# WaldoRevB.net
KiCad netlist of a schematic drawn in EAGLE
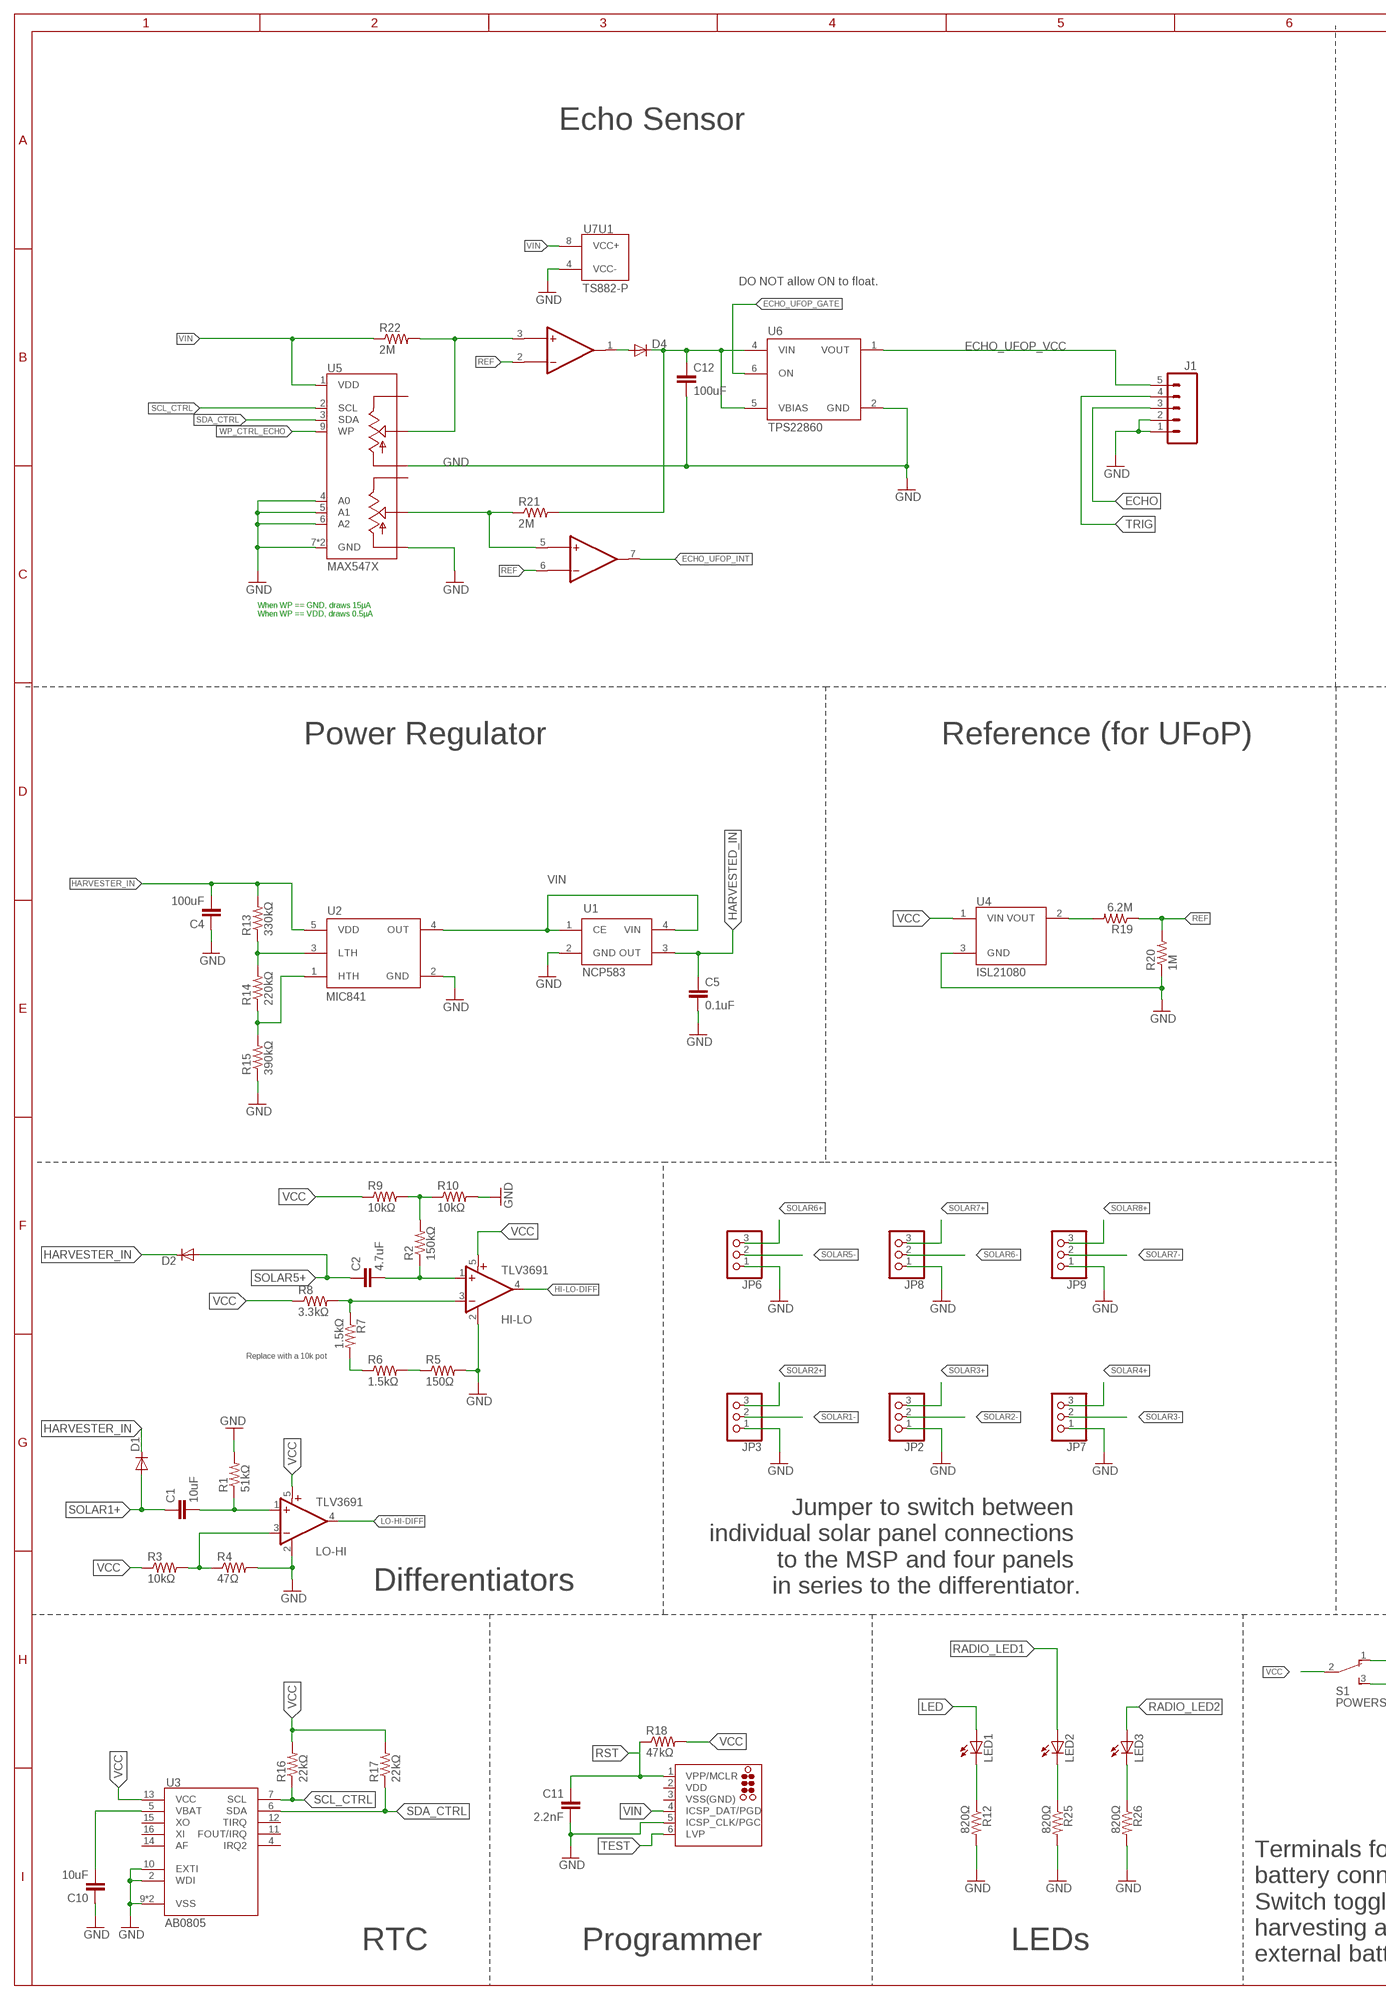
[diagram p0: schematic, sheet 1, part 1 of 2]
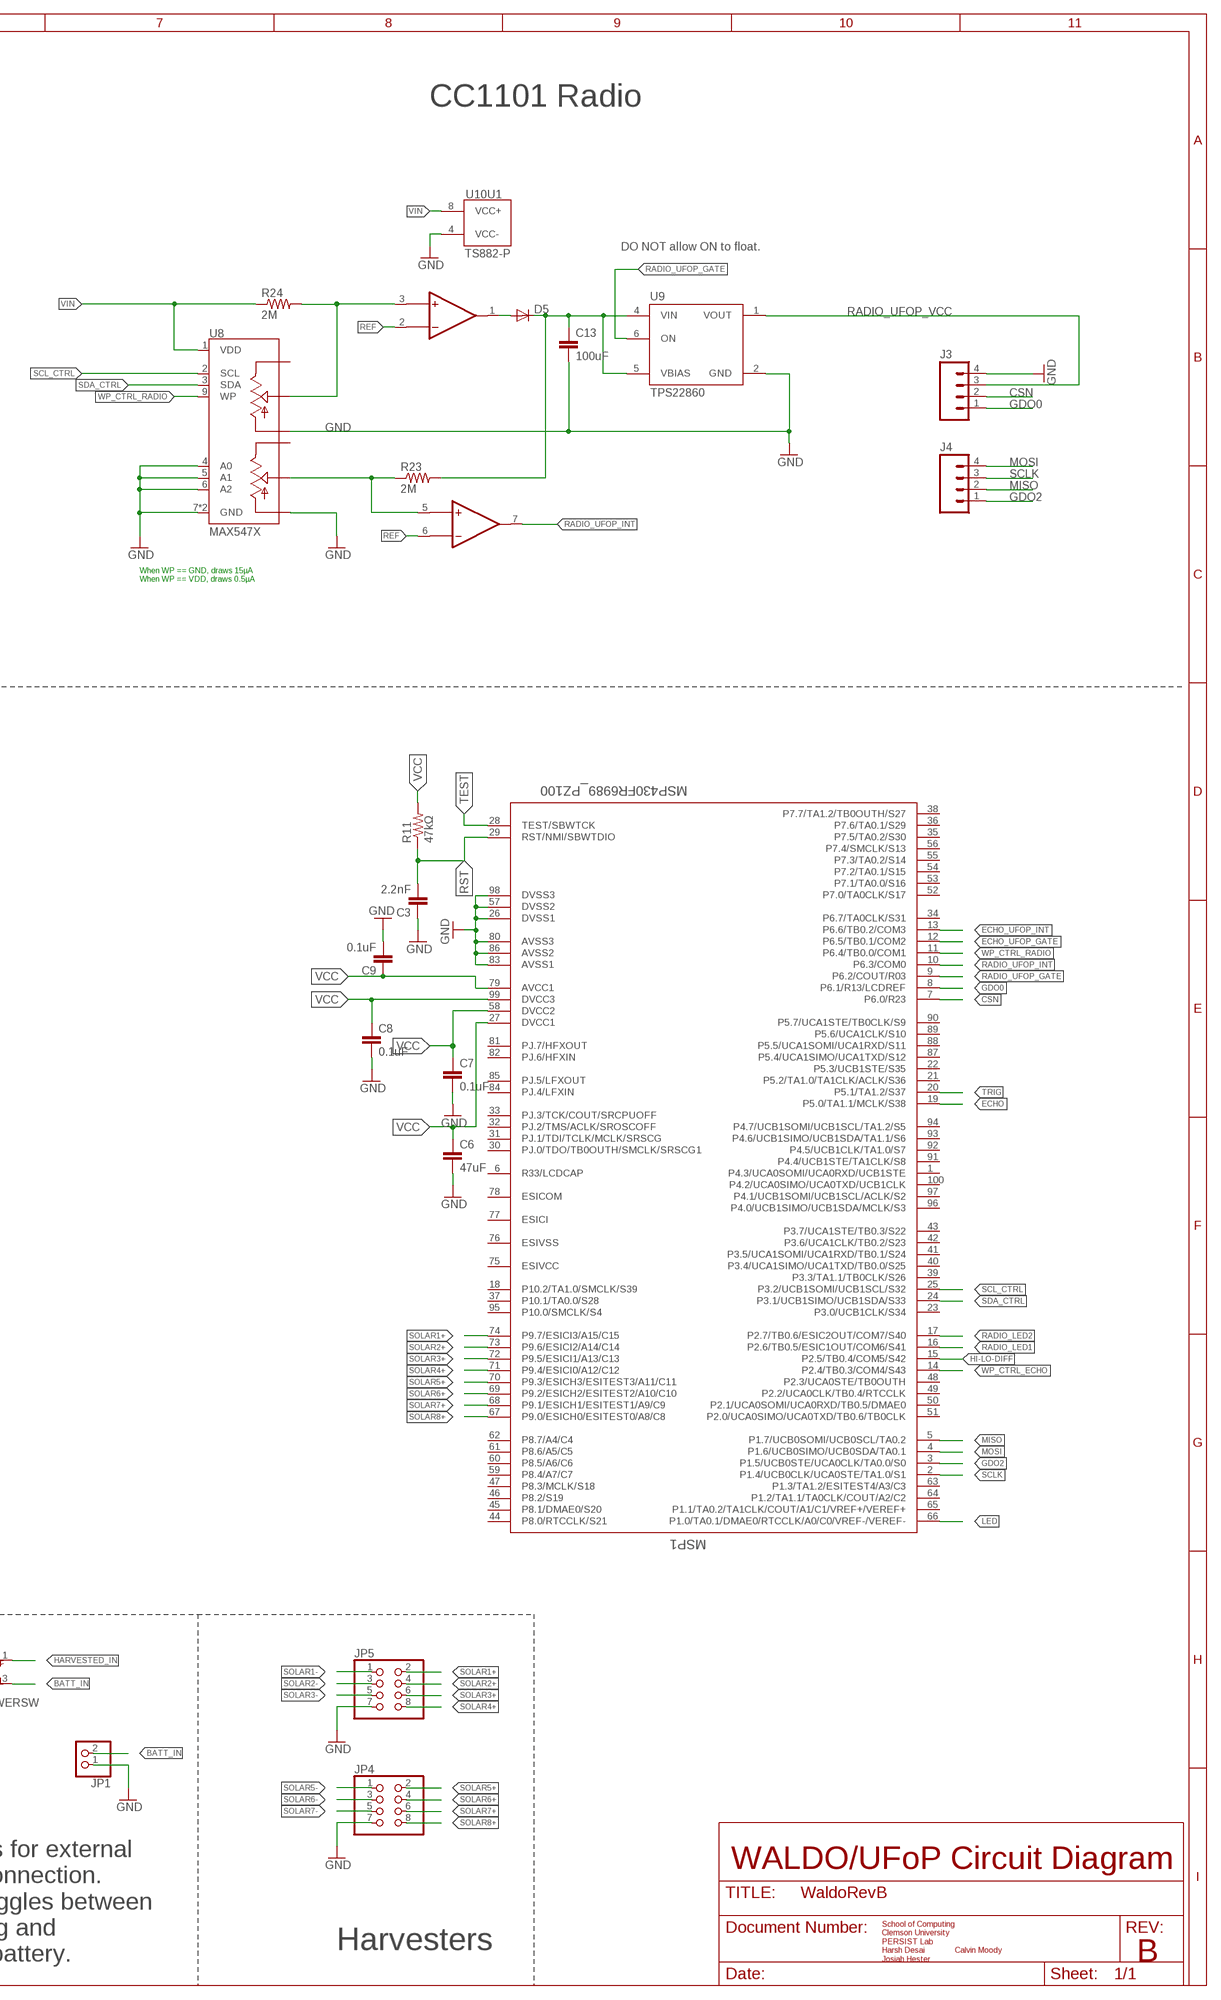
[diagram p1: schematic, sheet 1, part 2 of 2]

(export (version "E")
  (design (tool "Eeschema 10.0.6"))
  (components
    (comp (ref "C1")
      (value "10uF")
      (footprint "eagle-import:0805")
      (libsource (lib "eagle-import") (part "CAP0805"))
    )
    (comp (ref "C2")
      (value "4.7uF")
      (footprint "eagle-import:0805")
      (libsource (lib "eagle-import") (part "CAP0805"))
    )
    (comp (ref "C3")
      (value "2.2nF")
      (footprint "eagle-import:0805")
      (libsource (lib "eagle-import") (part "CAP0805"))
    )
    (comp (ref "C4")
      (value "100uF")
      (footprint "eagle-import:0805")
      (libsource (lib "eagle-import") (part "CAP0805"))
    )
    (comp (ref "C5")
      (value "0.1uF")
      (footprint "eagle-import:0805")
      (libsource (lib "eagle-import") (part "CAP0805"))
    )
    (comp (ref "C6")
      (value "47uF")
      (footprint "eagle-import:0805")
      (libsource (lib "eagle-import") (part "CAP0805"))
    )
    (comp (ref "C7")
      (value "0.1uF")
      (footprint "eagle-import:0805")
      (libsource (lib "eagle-import") (part "CAP0805"))
    )
    (comp (ref "C8")
      (value "0.1uF")
      (footprint "eagle-import:0805")
      (libsource (lib "eagle-import") (part "CAP0805"))
    )
    (comp (ref "C9")
      (value "0.1uF")
      (footprint "eagle-import:0805")
      (libsource (lib "eagle-import") (part "CAP0805"))
    )
    (comp (ref "C10")
      (value "10uF")
      (footprint "eagle-import:0805")
      (libsource (lib "eagle-import") (part "CAP0805"))
    )
    (comp (ref "C11")
      (value "2.2nF")
      (footprint "eagle-import:0805")
      (libsource (lib "eagle-import") (part "CAP0805"))
    )
    (comp (ref "C12")
      (value "100uF")
      (footprint "eagle-import:1210")
      (libsource (lib "eagle-import") (part "CAP1210"))
    )
    (comp (ref "C13")
      (value "100uF")
      (footprint "eagle-import:1210")
      (libsource (lib "eagle-import") (part "CAP1210"))
    )
    (comp (ref "D1")
      (value "DIODESOD523")
      (footprint "eagle-import:SOD523")
      (libsource (lib "eagle-import") (part "DIODESOD523"))
    )
    (comp (ref "D2")
      (value "DIODESOD523")
      (footprint "eagle-import:SOD523")
      (libsource (lib "eagle-import") (part "DIODESOD523"))
    )
    (comp (ref "D4")
      (value "DIODESOD")
      (footprint "eagle-import:SOD-323")
      (libsource (lib "eagle-import") (part "DIODESOD"))
    )
    (comp (ref "D5")
      (value "DIODESOD")
      (footprint "eagle-import:SOD-323")
      (libsource (lib "eagle-import") (part "DIODESOD"))
    )
    (comp (ref "HI-LO")
      (value "TLV3691")
      (footprint "eagle-import:SC70-5")
      (libsource (lib "eagle-import") (part "TLV3691"))
    )
    (comp (ref "J1")
      (value "M05PTH")
      (footprint "eagle-import:1X05")
      (libsource (lib "eagle-import") (part "M05PTH"))
    )
    (comp (ref "J2")
      (value "TC2030-MCP-NL")
      (footprint "eagle-import:TC2030-MCP-NL")
      (libsource (lib "eagle-import") (part "TC2030-MCP-NL"))
    )
    (comp (ref "J3")
      (value "M04PTH")
      (footprint "eagle-import:1X04")
      (libsource (lib "eagle-import") (part "M04PTH"))
    )
    (comp (ref "J4")
      (value "M04PTH")
      (footprint "eagle-import:1X04")
      (libsource (lib "eagle-import") (part "M04PTH"))
    )
    (comp (ref "JP1")
      (value "PINHD-1X2")
      (footprint "eagle-import:1X02")
      (libsource (lib "eagle-import") (part "PINHD-1X2"))
    )
    (comp (ref "JP2")
      (value "PINHD-1X3")
      (footprint "eagle-import:1X03")
      (libsource (lib "eagle-import") (part "PINHD-1X3"))
    )
    (comp (ref "JP3")
      (value "PINHD-1X3")
      (footprint "eagle-import:1X03")
      (libsource (lib "eagle-import") (part "PINHD-1X3"))
    )
    (comp (ref "JP4")
      (value "PINHD-2X4")
      (footprint "eagle-import:2X04")
      (libsource (lib "eagle-import") (part "PINHD-2X4"))
    )
    (comp (ref "JP5")
      (value "PINHD-2X4")
      (footprint "eagle-import:2X04")
      (libsource (lib "eagle-import") (part "PINHD-2X4"))
    )
    (comp (ref "JP6")
      (value "PINHD-1X3")
      (footprint "eagle-import:1X03")
      (libsource (lib "eagle-import") (part "PINHD-1X3"))
    )
    (comp (ref "JP7")
      (value "PINHD-1X3")
      (footprint "eagle-import:1X03")
      (libsource (lib "eagle-import") (part "PINHD-1X3"))
    )
    (comp (ref "JP8")
      (value "PINHD-1X3")
      (footprint "eagle-import:1X03")
      (libsource (lib "eagle-import") (part "PINHD-1X3"))
    )
    (comp (ref "JP9")
      (value "PINHD-1X3")
      (footprint "eagle-import:1X03")
      (libsource (lib "eagle-import") (part "PINHD-1X3"))
    )
    (comp (ref "LED1")
      (value "LEDCHIP-LED0805")
      (footprint "eagle-import:CHIP-LED0805")
      (libsource (lib "eagle-import") (part "LEDCHIP-LED0805"))
    )
    (comp (ref "LED2")
      (value "LEDCHIP-LED0805")
      (footprint "eagle-import:CHIP-LED0805")
      (libsource (lib "eagle-import") (part "LEDCHIP-LED0805"))
    )
    (comp (ref "LED3")
      (value "LEDCHIP-LED0805")
      (footprint "eagle-import:CHIP-LED0805")
      (libsource (lib "eagle-import") (part "LEDCHIP-LED0805"))
    )
    (comp (ref "LO-HI")
      (value "TLV3691")
      (footprint "eagle-import:SC70-5")
      (libsource (lib "eagle-import") (part "TLV3691"))
    )
    (comp (ref "MSP1")
      (value "MSP430FR6989_PZ100")
      (footprint "eagle-import:PZ100")
      (libsource (lib "eagle-import") (part "MSP430FR6989_PZ100"))
    )
    (comp (ref "R1")
      (value "51kΩ")
      (footprint "eagle-import:M0805")
      (libsource (lib "eagle-import") (part "R-US_M0805"))
    )
    (comp (ref "R2")
      (value "150kΩ")
      (footprint "eagle-import:M0805")
      (libsource (lib "eagle-import") (part "R-US_M0805"))
    )
    (comp (ref "R3")
      (value "10kΩ")
      (footprint "eagle-import:M0805")
      (libsource (lib "eagle-import") (part "R-US_M0805"))
    )
    (comp (ref "R4")
      (value "47Ω")
      (footprint "eagle-import:M0805")
      (libsource (lib "eagle-import") (part "R-US_M0805"))
    )
    (comp (ref "R5")
      (value "150Ω")
      (footprint "eagle-import:M0805")
      (libsource (lib "eagle-import") (part "R-US_M0805"))
    )
    (comp (ref "R6")
      (value "1.5kΩ")
      (footprint "eagle-import:M0805")
      (libsource (lib "eagle-import") (part "R-US_M0805"))
    )
    (comp (ref "R7")
      (value "1.5kΩ")
      (footprint "eagle-import:M0805")
      (libsource (lib "eagle-import") (part "R-US_M0805"))
    )
    (comp (ref "R8")
      (value "3.3kΩ")
      (footprint "eagle-import:M0805")
      (libsource (lib "eagle-import") (part "R-US_M0805"))
    )
    (comp (ref "R9")
      (value "10kΩ")
      (footprint "eagle-import:M0805")
      (libsource (lib "eagle-import") (part "R-US_M0805"))
    )
    (comp (ref "R10")
      (value "10kΩ")
      (footprint "eagle-import:M0805")
      (libsource (lib "eagle-import") (part "R-US_M0805"))
    )
    (comp (ref "R11")
      (value "47kΩ")
      (footprint "eagle-import:M0805")
      (libsource (lib "eagle-import") (part "R-US_M0805"))
    )
    (comp (ref "R12")
      (value "820Ω")
      (footprint "eagle-import:M0805")
      (libsource (lib "eagle-import") (part "R-US_M0805"))
    )
    (comp (ref "R13")
      (value "330kΩ")
      (footprint "eagle-import:M0805")
      (libsource (lib "eagle-import") (part "R-US_M0805"))
    )
    (comp (ref "R14")
      (value "220kΩ")
      (footprint "eagle-import:M0805")
      (libsource (lib "eagle-import") (part "R-US_M0805"))
    )
    (comp (ref "R15")
      (value "390kΩ")
      (footprint "eagle-import:M0805")
      (libsource (lib "eagle-import") (part "R-US_M0805"))
    )
    (comp (ref "R16")
      (value "22kΩ")
      (footprint "eagle-import:M0805")
      (libsource (lib "eagle-import") (part "R-US_M0805"))
    )
    (comp (ref "R17")
      (value "22kΩ")
      (footprint "eagle-import:M0805")
      (libsource (lib "eagle-import") (part "R-US_M0805"))
    )
    (comp (ref "R18")
      (value "47kΩ")
      (footprint "eagle-import:M0805")
      (libsource (lib "eagle-import") (part "R-US_M0805"))
    )
    (comp (ref "R19")
      (value "6.2M")
      (footprint "eagle-import:0603")
      (libsource (lib "eagle-import") (part "R-EU0603"))
    )
    (comp (ref "R20")
      (value "1M")
      (footprint "eagle-import:0603")
      (libsource (lib "eagle-import") (part "R-EU0603"))
    )
    (comp (ref "R21")
      (value "2M")
      (footprint "eagle-import:0603")
      (libsource (lib "eagle-import") (part "R-EU0603"))
    )
    (comp (ref "R22")
      (value "2M")
      (footprint "eagle-import:0603")
      (libsource (lib "eagle-import") (part "R-EU0603"))
    )
    (comp (ref "R23")
      (value "2M")
      (footprint "eagle-import:0603")
      (libsource (lib "eagle-import") (part "R-EU0603"))
    )
    (comp (ref "R24")
      (value "2M")
      (footprint "eagle-import:0603")
      (libsource (lib "eagle-import") (part "R-EU0603"))
    )
    (comp (ref "R25")
      (value "820Ω")
      (footprint "eagle-import:M0805")
      (libsource (lib "eagle-import") (part "R-US_M0805"))
    )
    (comp (ref "R26")
      (value "820Ω")
      (footprint "eagle-import:M0805")
      (libsource (lib "eagle-import") (part "R-US_M0805"))
    )
    (comp (ref "S1")
      (value "POWERSW")
      (footprint "eagle-import:TL3XYO")
      (libsource (lib "eagle-import") (part "POWERSW"))
    )
    (comp (ref "U1")
      (value "NCP583")
      (footprint "eagle-import:SC82-AB_1PRIMARY")
      (libsource (lib "eagle-import") (part "NCP583"))
    )
    (comp (ref "U2")
      (value "MIC841")
      (footprint "eagle-import:SC70-5")
      (libsource (lib "eagle-import") (part "MIC841"))
    )
    (comp (ref "U3")
      (value "AB0805")
      (footprint "eagle-import:QFN16")
      (libsource (lib "eagle-import") (part "AB0805"))
    )
    (comp (ref "U4")
      (value "ISL21080")
      (footprint "eagle-import:SOT-23")
      (libsource (lib "eagle-import") (part "ISL21080"))
    )
    (comp (ref "U5")
      (value "MAX547X")
      (footprint "eagle-import:QFN16")
      (libsource (lib "eagle-import") (part "MAX547X"))
    )
    (comp (ref "U6")
      (value "TPS22860")
      (footprint "eagle-import:TSOT23-6")
      (libsource (lib "eagle-import") (part "TPS22860"))
    )
    (comp (ref "U7")
      (value "TS882-P")
      (footprint "eagle-import:UDFN8")
      (fields (field (name "DIGIKEY") "497-14073-1-ND"))
      (libsource (lib "eagle-import") (part "TS882-P"))
    )
    (comp (ref "U8")
      (value "MAX547X")
      (footprint "eagle-import:QFN16")
      (libsource (lib "eagle-import") (part "MAX547X"))
    )
    (comp (ref "U9")
      (value "TPS22860")
      (footprint "eagle-import:TSOT23-6")
      (libsource (lib "eagle-import") (part "TPS22860"))
    )
    (comp (ref "U10")
      (value "TS882-P")
      (footprint "eagle-import:UDFN8")
      (fields (field (name "DIGIKEY") "497-14073-1-ND"))
      (libsource (lib "eagle-import") (part "TS882-P"))
    )
  )
  (nets
    (net (code "1") (name "/ECHO_UFOP_VCC") (class "Default")
      (node (ref "J1") (pin "5") (pinfunction "5_5") (pintype "passive"))
      (node (ref "U6") (pin "1") (pinfunction "VOUT_1") (pintype "bidirectional"))
    )
    (net (code "2") (name "/RADIO_UFOP_VCC") (class "Default")
      (node (ref "J3") (pin "3") (pinfunction "3_3") (pintype "passive"))
      (node (ref "U9") (pin "1") (pinfunction "VOUT_1") (pintype "bidirectional"))
    )
    (net (code "3") (name "/VDD") (class "Default")
      (node (ref "J2") (pin "2") (pinfunction "VDD_2") (pintype "power_in"))
    )
    (net (code "4") (name "/VSS(GND)") (class "Default")
      (node (ref "J2") (pin "3") (pinfunction "VSS(GND)_3") (pintype "power_in"))
    )
    (net (code "5") (name "BATT_IN") (class "Default")
      (node (ref "JP1") (pin "2") (pinfunction "2_2") (pintype "passive"))
      (node (ref "S1") (pin "3") (pinfunction "S_3") (pintype "passive"))
    )
    (net (code "6") (name "CSN") (class "Default")
      (node (ref "J3") (pin "2") (pinfunction "2_2") (pintype "passive"))
      (node (ref "MSP1") (pin "7") (pinfunction "P6.0/R23_7") (pintype "bidirectional"))
    )
    (net (code "7") (name "ECHO") (class "Default")
      (node (ref "J1") (pin "3") (pinfunction "3_3") (pintype "passive"))
      (node (ref "MSP1") (pin "19") (pinfunction "P5.0/TA1.1/MCLK/S38_19") (pintype "bidirectional"))
    )
    (net (code "8") (name "ECHO_UFOP_GATE") (class "Default")
      (node (ref "MSP1") (pin "12") (pinfunction "P6.5/TB0.1/COM2_12") (pintype "bidirectional"))
      (node (ref "U6") (pin "6") (pinfunction "ON_6") (pintype "bidirectional"))
    )
    (net (code "9") (name "ECHO_UFOP_INT") (class "Default")
      (node (ref "MSP1") (pin "13") (pinfunction "P6.6/TB0.2/COM3_13") (pintype "bidirectional"))
      (node (ref "U7") (pin "7") (pinfunction "OUT1_7") (pintype "output"))
    )
    (net (code "10") (name "GDO0") (class "Default")
      (node (ref "J3") (pin "1") (pinfunction "1_1") (pintype "passive"))
      (node (ref "MSP1") (pin "8") (pinfunction "P6.1/R13/LCDREF_8") (pintype "bidirectional"))
    )
    (net (code "11") (name "GDO2") (class "Default")
      (node (ref "J4") (pin "1") (pinfunction "1_1") (pintype "passive"))
      (node (ref "MSP1") (pin "3") (pinfunction "P1.5/UCB0STE/UCA0CLK/TA0.0/S0_3") (pintype "bidirectional"))
    )
    (net (code "12") (name "GND") (class "Default")
      (node (ref "C10") (pin "1") (pinfunction "1_1") (pintype "passive"))
      (node (ref "C11") (pin "2") (pinfunction "2_2") (pintype "passive"))
      (node (ref "C12") (pin "2") (pinfunction "2_2") (pintype "passive"))
      (node (ref "C13") (pin "2") (pinfunction "2_2") (pintype "passive"))
      (node (ref "C3") (pin "1") (pinfunction "1_1") (pintype "passive"))
      (node (ref "C4") (pin "1") (pinfunction "1_1") (pintype "passive"))
      (node (ref "C5") (pin "2") (pinfunction "2_2") (pintype "passive"))
      (node (ref "C6") (pin "2") (pinfunction "2_2") (pintype "passive"))
      (node (ref "C7") (pin "2") (pinfunction "2_2") (pintype "passive"))
      (node (ref "C8") (pin "2") (pinfunction "2_2") (pintype "passive"))
      (node (ref "C9") (pin "2") (pinfunction "2_2") (pintype "passive"))
      (node (ref "HI-LO") (pin "2") (pinfunction "GND_2") (pintype "power_in"))
      (node (ref "J1") (pin "1") (pinfunction "1_1") (pintype "passive"))
      (node (ref "J1") (pin "2") (pinfunction "2_2") (pintype "passive"))
      (node (ref "J2") (pin "5") (pinfunction "ICSP_CLK/PGC_5") (pintype "output"))
      (node (ref "J3") (pin "4") (pinfunction "4_4") (pintype "passive"))
      (node (ref "JP1") (pin "1") (pinfunction "1_1") (pintype "passive"))
      (node (ref "JP2") (pin "1") (pinfunction "1_1") (pintype "passive"))
      (node (ref "JP3") (pin "1") (pinfunction "1_1") (pintype "passive"))
      (node (ref "JP4") (pin "7") (pinfunction "7_7") (pintype "passive"))
      (node (ref "JP5") (pin "7") (pinfunction "7_7") (pintype "passive"))
      (node (ref "JP6") (pin "1") (pinfunction "1_1") (pintype "passive"))
      (node (ref "JP7") (pin "1") (pinfunction "1_1") (pintype "passive"))
      (node (ref "JP8") (pin "1") (pinfunction "1_1") (pintype "passive"))
      (node (ref "JP9") (pin "1") (pinfunction "1_1") (pintype "passive"))
      (node (ref "LO-HI") (pin "2") (pinfunction "GND_2") (pintype "power_in"))
      (node (ref "MSP1") (pin "26") (pinfunction "DVSS1_26") (pintype "bidirectional"))
      (node (ref "MSP1") (pin "57") (pinfunction "DVSS2_57") (pintype "bidirectional"))
      (node (ref "MSP1") (pin "80") (pinfunction "AVSS3_80") (pintype "bidirectional"))
      (node (ref "MSP1") (pin "83") (pinfunction "AVSS1_83") (pintype "bidirectional"))
      (node (ref "MSP1") (pin "86") (pinfunction "AVSS2_86") (pintype "bidirectional"))
      (node (ref "MSP1") (pin "98") (pinfunction "DVSS3_98") (pintype "bidirectional"))
      (node (ref "R1") (pin "2") (pinfunction "2_2") (pintype "passive"))
      (node (ref "R10") (pin "2") (pinfunction "2_2") (pintype "passive"))
      (node (ref "R12") (pin "2") (pinfunction "2_2") (pintype "passive"))
      (node (ref "R15") (pin "1") (pinfunction "1_1") (pintype "passive"))
      (node (ref "R20") (pin "1") (pinfunction "1_1") (pintype "passive"))
      (node (ref "R25") (pin "2") (pinfunction "2_2") (pintype "passive"))
      (node (ref "R26") (pin "2") (pinfunction "2_2") (pintype "passive"))
      (node (ref "R4") (pin "2") (pinfunction "2_2") (pintype "passive"))
      (node (ref "R5") (pin "2") (pinfunction "2_2") (pintype "passive"))
      (node (ref "U1") (pin "2") (pinfunction "GND_2") (pintype "bidirectional"))
      (node (ref "U10") (pin "4") (pinfunction "VCC-_4") (pintype "bidirectional"))
      (node (ref "U2") (pin "2") (pinfunction "GND_2") (pintype "bidirectional"))
      (node (ref "U3") (pin "10") (pinfunction "EXTI_10") (pintype "bidirectional"))
      (node (ref "U3") (pin "2") (pinfunction "WDI_2") (pintype "bidirectional"))
      (node (ref "U3") (pin "9") (pinfunction "VSS_9") (pintype "bidirectional"))
      (node (ref "U3") (pin "TH") (pinfunction "VSS_TH") (pintype "bidirectional"))
      (node (ref "U4") (pin "3") (pinfunction "GND_3") (pintype "bidirectional"))
      (node (ref "U5") (pin "10") (pinfunction "LB_10") (pintype "bidirectional"))
      (node (ref "U5") (pin "13") (pinfunction "LA_13") (pintype "passive"))
      (node (ref "U5") (pin "4") (pinfunction "A0_4") (pintype "bidirectional"))
      (node (ref "U5") (pin "5") (pinfunction "A1_5") (pintype "bidirectional"))
      (node (ref "U5") (pin "6") (pinfunction "A2_6") (pintype "bidirectional"))
      (node (ref "U5") (pin "7") (pinfunction "GND_7") (pintype "bidirectional"))
      (node (ref "U5") (pin "TH") (pinfunction "GND_TH") (pintype "bidirectional"))
      (node (ref "U6") (pin "2") (pinfunction "GND_2") (pintype "bidirectional"))
      (node (ref "U7") (pin "4") (pinfunction "VCC-_4") (pintype "bidirectional"))
      (node (ref "U8") (pin "10") (pinfunction "LB_10") (pintype "bidirectional"))
      (node (ref "U8") (pin "13") (pinfunction "LA_13") (pintype "passive"))
      (node (ref "U8") (pin "4") (pinfunction "A0_4") (pintype "bidirectional"))
      (node (ref "U8") (pin "5") (pinfunction "A1_5") (pintype "bidirectional"))
      (node (ref "U8") (pin "6") (pinfunction "A2_6") (pintype "bidirectional"))
      (node (ref "U8") (pin "7") (pinfunction "GND_7") (pintype "bidirectional"))
      (node (ref "U8") (pin "TH") (pinfunction "GND_TH") (pintype "bidirectional"))
      (node (ref "U9") (pin "2") (pinfunction "GND_2") (pintype "bidirectional"))
    )
    (net (code "13") (name "HARVESTED_IN") (class "Default")
      (node (ref "C5") (pin "1") (pinfunction "1_1") (pintype "passive"))
      (node (ref "S1") (pin "1") (pinfunction "O_1") (pintype "passive"))
      (node (ref "U1") (pin "3") (pinfunction "OUT_3") (pintype "bidirectional"))
    )
    (net (code "14") (name "HARVESTER_IN") (class "Default")
      (node (ref "C4") (pin "2") (pinfunction "2_2") (pintype "passive"))
      (node (ref "D1") (pin "C") (pinfunction "C_C") (pintype "passive"))
      (node (ref "D2") (pin "C") (pinfunction "C_C") (pintype "passive"))
      (node (ref "R13") (pin "2") (pinfunction "2_2") (pintype "passive"))
      (node (ref "U2") (pin "5") (pinfunction "VDD_5") (pintype "bidirectional"))
    )
    (net (code "15") (name "HI-LO-DIFF") (class "Default")
      (node (ref "HI-LO") (pin "4") (pinfunction "OUT_4") (pintype "output"))
      (node (ref "MSP1") (pin "15") (pinfunction "P2.5/TB0.4/COM5/S42_15") (pintype "bidirectional"))
    )
    (net (code "16") (name "LED") (class "Default")
      (node (ref "LED1") (pin "A") (pinfunction "A_A") (pintype "passive"))
      (node (ref "MSP1") (pin "66") (pinfunction "P1.0/TA0.1/DMAE0/RTCCLK/A0/C0/VREF-/VEREF-_66") (pintype "bidirectional"))
    )
    (net (code "17") (name "LO-HI-DIFF") (class "Default")
      (node (ref "LO-HI") (pin "4") (pinfunction "OUT_4") (pintype "output"))
    )
    (net (code "18") (name "MISO") (class "Default")
      (node (ref "J4") (pin "2") (pinfunction "2_2") (pintype "passive"))
      (node (ref "MSP1") (pin "5") (pinfunction "P1.7/UCB0SOMI/UCB0SCL/TA0.2_5") (pintype "bidirectional"))
    )
    (net (code "19") (name "MOSI") (class "Default")
      (node (ref "J4") (pin "4") (pinfunction "4_4") (pintype "passive"))
      (node (ref "MSP1") (pin "4") (pinfunction "P1.6/UCB0SIMO/UCB0SDA/TA0.1_4") (pintype "bidirectional"))
    )
    (net (code "20") (name "Net-(D4-A)") (class "Default")
      (node (ref "D4") (pin "2") (pinfunction "A_2") (pintype "passive"))
      (node (ref "U7") (pin "1") (pinfunction "OUT1_1") (pintype "output"))
    )
    (net (code "21") (name "Net-(D4-C)") (class "Default")
      (node (ref "C12") (pin "1") (pinfunction "1_1") (pintype "passive"))
      (node (ref "D4") (pin "1") (pinfunction "C_1") (pintype "passive"))
      (node (ref "R21") (pin "2") (pinfunction "2_2") (pintype "passive"))
      (node (ref "U6") (pin "4") (pinfunction "VIN_4") (pintype "bidirectional"))
      (node (ref "U6") (pin "5") (pinfunction "VBIAS_5") (pintype "bidirectional"))
    )
    (net (code "22") (name "Net-(D5-A)") (class "Default")
      (node (ref "D5") (pin "2") (pinfunction "A_2") (pintype "passive"))
      (node (ref "U10") (pin "1") (pinfunction "OUT1_1") (pintype "output"))
    )
    (net (code "23") (name "Net-(D5-C)") (class "Default")
      (node (ref "C13") (pin "1") (pinfunction "1_1") (pintype "passive"))
      (node (ref "D5") (pin "1") (pinfunction "C_1") (pintype "passive"))
      (node (ref "R23") (pin "2") (pinfunction "2_2") (pintype "passive"))
      (node (ref "U9") (pin "4") (pinfunction "VIN_4") (pintype "bidirectional"))
      (node (ref "U9") (pin "5") (pinfunction "VBIAS_5") (pintype "bidirectional"))
    )
    (net (code "24") (name "Net-(HI-LO-+IN)") (class "Default")
      (node (ref "C2") (pin "2") (pinfunction "2_2") (pintype "passive"))
      (node (ref "HI-LO") (pin "1") (pinfunction "+IN_1") (pintype "input"))
      (node (ref "R2") (pin "1") (pinfunction "1_1") (pintype "passive"))
    )
    (net (code "25") (name "Net-(HI-LO--IN)") (class "Default")
      (node (ref "HI-LO") (pin "3") (pinfunction "-IN_3") (pintype "input"))
      (node (ref "R7") (pin "1") (pinfunction "1_1") (pintype "passive"))
      (node (ref "R8") (pin "2") (pinfunction "2_2") (pintype "passive"))
    )
    (net (code "26") (name "Net-(LED1-PadC)") (class "Default")
      (node (ref "LED1") (pin "C") (pinfunction "C_C") (pintype "passive"))
      (node (ref "R12") (pin "1") (pinfunction "1_1") (pintype "passive"))
    )
    (net (code "27") (name "Net-(LED2-PadC)") (class "Default")
      (node (ref "LED2") (pin "C") (pinfunction "C_C") (pintype "passive"))
      (node (ref "R25") (pin "1") (pinfunction "1_1") (pintype "passive"))
    )
    (net (code "28") (name "Net-(LED3-PadC)") (class "Default")
      (node (ref "LED3") (pin "C") (pinfunction "C_C") (pintype "passive"))
      (node (ref "R26") (pin "1") (pinfunction "1_1") (pintype "passive"))
    )
    (net (code "29") (name "Net-(LO-HI-+IN)") (class "Default")
      (node (ref "C1") (pin "2") (pinfunction "2_2") (pintype "passive"))
      (node (ref "LO-HI") (pin "1") (pinfunction "+IN_1") (pintype "input"))
      (node (ref "R1") (pin "1") (pinfunction "1_1") (pintype "passive"))
    )
    (net (code "30") (name "Net-(LO-HI--IN)") (class "Default")
      (node (ref "LO-HI") (pin "3") (pinfunction "-IN_3") (pintype "input"))
      (node (ref "R3") (pin "2") (pinfunction "2_2") (pintype "passive"))
      (node (ref "R4") (pin "1") (pinfunction "1_1") (pintype "passive"))
    )
    (net (code "31") (name "Net-(R5-Pad1)") (class "Default")
      (node (ref "R5") (pin "1") (pinfunction "1_1") (pintype "passive"))
      (node (ref "R6") (pin "2") (pinfunction "2_2") (pintype "passive"))
    )
    (net (code "32") (name "Net-(R6-Pad1)") (class "Default")
      (node (ref "R6") (pin "1") (pinfunction "1_1") (pintype "passive"))
      (node (ref "R7") (pin "2") (pinfunction "2_2") (pintype "passive"))
    )
    (net (code "33") (name "Net-(R10-Pad1)") (class "Default")
      (node (ref "R10") (pin "1") (pinfunction "1_1") (pintype "passive"))
      (node (ref "R2") (pin "2") (pinfunction "2_2") (pintype "passive"))
      (node (ref "R9") (pin "2") (pinfunction "2_2") (pintype "passive"))
    )
    (net (code "34") (name "Net-(U2-HTH)") (class "Default")
      (node (ref "R14") (pin "1") (pinfunction "1_1") (pintype "passive"))
      (node (ref "R15") (pin "2") (pinfunction "2_2") (pintype "passive"))
      (node (ref "U2") (pin "1") (pinfunction "HTH_1") (pintype "bidirectional"))
    )
    (net (code "35") (name "Net-(U2-LTH)") (class "Default")
      (node (ref "R13") (pin "1") (pinfunction "1_1") (pintype "passive"))
      (node (ref "R14") (pin "2") (pinfunction "2_2") (pintype "passive"))
      (node (ref "U2") (pin "3") (pinfunction "LTH_3") (pintype "bidirectional"))
    )
    (net (code "36") (name "Net-(U3-VBAT)") (class "Default")
      (node (ref "C10") (pin "2") (pinfunction "2_2") (pintype "passive"))
      (node (ref "U3") (pin "5") (pinfunction "VBAT_5") (pintype "bidirectional"))
    )
    (net (code "37") (name "Net-(U4-VOUT)") (class "Default")
      (node (ref "R19") (pin "2") (pinfunction "2_2") (pintype "passive"))
      (node (ref "U4") (pin "2") (pinfunction "VOUT_2") (pintype "bidirectional"))
    )
    (net (code "38") (name "Net-(U5-WA)") (class "Default")
      (node (ref "R22") (pin "2") (pinfunction "2_2") (pintype "passive"))
      (node (ref "U5") (pin "14") (pinfunction "WA_14") (pintype "passive"))
      (node (ref "U7") (pin "3") (pinfunction "IN1+_3") (pintype "input"))
    )
    (net (code "39") (name "Net-(U5-WB)") (class "Default")
      (node (ref "R21") (pin "1") (pinfunction "1_1") (pintype "passive"))
      (node (ref "U5") (pin "11") (pinfunction "WB_11") (pintype "bidirectional"))
      (node (ref "U7") (pin "5") (pinfunction "IN1+_5") (pintype "input"))
    )
    (net (code "40") (name "Net-(U10A-IN1+)") (class "Default")
      (node (ref "R24") (pin "2") (pinfunction "2_2") (pintype "passive"))
      (node (ref "U10") (pin "3") (pinfunction "IN1+_3") (pintype "input"))
      (node (ref "U8") (pin "14") (pinfunction "WA_14") (pintype "passive"))
    )
    (net (code "41") (name "Net-(U10B-IN1+)") (class "Default")
      (node (ref "R23") (pin "1") (pinfunction "1_1") (pintype "passive"))
      (node (ref "U10") (pin "5") (pinfunction "IN1+_5") (pintype "input"))
      (node (ref "U8") (pin "11") (pinfunction "WB_11") (pintype "bidirectional"))
    )
    (net (code "42") (name "RADIO_LED1") (class "Default")
      (node (ref "LED2") (pin "A") (pinfunction "A_A") (pintype "passive"))
      (node (ref "MSP1") (pin "16") (pinfunction "P2.6/TB0.5/ESIC1OUT/COM6/S41_16") (pintype "bidirectional"))
    )
    (net (code "43") (name "RADIO_LED2") (class "Default")
      (node (ref "LED3") (pin "A") (pinfunction "A_A") (pintype "passive"))
      (node (ref "MSP1") (pin "17") (pinfunction "P2.7/TB0.6/ESIC2OUT/COM7/S40_17") (pintype "bidirectional"))
    )
    (net (code "44") (name "RADIO_UFOP_GATE") (class "Default")
      (node (ref "MSP1") (pin "9") (pinfunction "P6.2/COUT/R03_9") (pintype "bidirectional"))
      (node (ref "U9") (pin "6") (pinfunction "ON_6") (pintype "bidirectional"))
    )
    (net (code "45") (name "RADIO_UFOP_INT") (class "Default")
      (node (ref "MSP1") (pin "10") (pinfunction "P6.3/COM0_10") (pintype "bidirectional"))
      (node (ref "U10") (pin "7") (pinfunction "OUT1_7") (pintype "output"))
    )
    (net (code "46") (name "REF") (class "Default")
      (node (ref "R19") (pin "1") (pinfunction "1_1") (pintype "passive"))
      (node (ref "R20") (pin "2") (pinfunction "2_2") (pintype "passive"))
      (node (ref "U10") (pin "2") (pinfunction "IN1-_2") (pintype "input"))
      (node (ref "U10") (pin "6") (pinfunction "IN1-_6") (pintype "input"))
      (node (ref "U7") (pin "2") (pinfunction "IN1-_2") (pintype "input"))
      (node (ref "U7") (pin "6") (pinfunction "IN1-_6") (pintype "input"))
    )
    (net (code "47") (name "RST") (class "Default")
      (node (ref "C11") (pin "1") (pinfunction "1_1") (pintype "passive"))
      (node (ref "C3") (pin "2") (pinfunction "2_2") (pintype "passive"))
      (node (ref "J2") (pin "1") (pinfunction "VPP/MCLR_1") (pintype "passive"))
      (node (ref "MSP1") (pin "29") (pinfunction "RST/NMI/SBWTDIO_29") (pintype "bidirectional"))
      (node (ref "R11") (pin "1") (pinfunction "1_1") (pintype "passive"))
      (node (ref "R18") (pin "1") (pinfunction "1_1") (pintype "passive"))
    )
    (net (code "48") (name "SCLK") (class "Default")
      (node (ref "J4") (pin "3") (pinfunction "3_3") (pintype "passive"))
      (node (ref "MSP1") (pin "2") (pinfunction "P1.4/UCB0CLK/UCA0STE/TA1.0/S1_2") (pintype "bidirectional"))
    )
    (net (code "49") (name "SCL_CTRL") (class "Default")
      (node (ref "MSP1") (pin "25") (pinfunction "P3.2/UCB1SOMI/UCB1SCL/S32_25") (pintype "bidirectional"))
      (node (ref "R16") (pin "1") (pinfunction "1_1") (pintype "passive"))
      (node (ref "U3") (pin "7") (pinfunction "SCL_7") (pintype "bidirectional"))
      (node (ref "U5") (pin "2") (pinfunction "SCL_2") (pintype "bidirectional"))
      (node (ref "U8") (pin "2") (pinfunction "SCL_2") (pintype "bidirectional"))
    )
    (net (code "50") (name "SDA_CTRL") (class "Default")
      (node (ref "MSP1") (pin "24") (pinfunction "P3.1/UCB1SIMO/UCB1SDA/S33_24") (pintype "bidirectional"))
      (node (ref "R17") (pin "1") (pinfunction "1_1") (pintype "passive"))
      (node (ref "U3") (pin "6") (pinfunction "SDA_6") (pintype "bidirectional"))
      (node (ref "U5") (pin "3") (pinfunction "SDA_3") (pintype "bidirectional"))
      (node (ref "U8") (pin "3") (pinfunction "SDA_3") (pintype "bidirectional"))
    )
    (net (code "51") (name "SOLAR1+") (class "Default")
      (node (ref "C1") (pin "1") (pinfunction "1_1") (pintype "passive"))
      (node (ref "D1") (pin "A") (pinfunction "A_A") (pintype "passive"))
      (node (ref "JP5") (pin "2") (pinfunction "2_2") (pintype "passive"))
      (node (ref "MSP1") (pin "74") (pinfunction "P9.7/ESICI3/A15/C15_74") (pintype "bidirectional"))
    )
    (net (code "52") (name "SOLAR1-") (class "Default")
      (node (ref "JP3") (pin "2") (pinfunction "2_2") (pintype "passive"))
      (node (ref "JP5") (pin "1") (pinfunction "1_1") (pintype "passive"))
    )
    (net (code "53") (name "SOLAR2+") (class "Default")
      (node (ref "JP3") (pin "3") (pinfunction "3_3") (pintype "passive"))
      (node (ref "JP5") (pin "4") (pinfunction "4_4") (pintype "passive"))
      (node (ref "MSP1") (pin "73") (pinfunction "P9.6/ESICI2/A14/C14_73") (pintype "bidirectional"))
    )
    (net (code "54") (name "SOLAR2-") (class "Default")
      (node (ref "JP2") (pin "2") (pinfunction "2_2") (pintype "passive"))
      (node (ref "JP5") (pin "3") (pinfunction "3_3") (pintype "passive"))
    )
    (net (code "55") (name "SOLAR3+") (class "Default")
      (node (ref "JP2") (pin "3") (pinfunction "3_3") (pintype "passive"))
      (node (ref "JP5") (pin "6") (pinfunction "6_6") (pintype "passive"))
      (node (ref "MSP1") (pin "72") (pinfunction "P9.5/ESICI1/A13/C13_72") (pintype "bidirectional"))
    )
    (net (code "56") (name "SOLAR3-") (class "Default")
      (node (ref "JP5") (pin "5") (pinfunction "5_5") (pintype "passive"))
      (node (ref "JP7") (pin "2") (pinfunction "2_2") (pintype "passive"))
    )
    (net (code "57") (name "SOLAR4+") (class "Default")
      (node (ref "JP5") (pin "8") (pinfunction "8_8") (pintype "passive"))
      (node (ref "JP7") (pin "3") (pinfunction "3_3") (pintype "passive"))
      (node (ref "MSP1") (pin "71") (pinfunction "P9.4/ESICI0/A12/C12_71") (pintype "bidirectional"))
    )
    (net (code "58") (name "SOLAR5+") (class "Default")
      (node (ref "C2") (pin "1") (pinfunction "1_1") (pintype "passive"))
      (node (ref "D2") (pin "A") (pinfunction "A_A") (pintype "passive"))
      (node (ref "JP4") (pin "2") (pinfunction "2_2") (pintype "passive"))
      (node (ref "MSP1") (pin "70") (pinfunction "P9.3/ESICH3/ESITEST3/A11/C11_70") (pintype "bidirectional"))
    )
    (net (code "59") (name "SOLAR5-") (class "Default")
      (node (ref "JP4") (pin "1") (pinfunction "1_1") (pintype "passive"))
      (node (ref "JP6") (pin "2") (pinfunction "2_2") (pintype "passive"))
    )
    (net (code "60") (name "SOLAR6+") (class "Default")
      (node (ref "JP4") (pin "4") (pinfunction "4_4") (pintype "passive"))
      (node (ref "JP6") (pin "3") (pinfunction "3_3") (pintype "passive"))
      (node (ref "MSP1") (pin "69") (pinfunction "P9.2/ESICH2/ESITEST2/A10/C10_69") (pintype "bidirectional"))
    )
    (net (code "61") (name "SOLAR6-") (class "Default")
      (node (ref "JP4") (pin "3") (pinfunction "3_3") (pintype "passive"))
      (node (ref "JP8") (pin "2") (pinfunction "2_2") (pintype "passive"))
    )
    (net (code "62") (name "SOLAR7+") (class "Default")
      (node (ref "JP4") (pin "6") (pinfunction "6_6") (pintype "passive"))
      (node (ref "JP8") (pin "3") (pinfunction "3_3") (pintype "passive"))
      (node (ref "MSP1") (pin "68") (pinfunction "P9.1/ESICH1/ESITEST1/A9/C9_68") (pintype "bidirectional"))
    )
    (net (code "63") (name "SOLAR7-") (class "Default")
      (node (ref "JP4") (pin "5") (pinfunction "5_5") (pintype "passive"))
      (node (ref "JP9") (pin "2") (pinfunction "2_2") (pintype "passive"))
    )
    (net (code "64") (name "SOLAR8+") (class "Default")
      (node (ref "JP4") (pin "8") (pinfunction "8_8") (pintype "passive"))
      (node (ref "JP9") (pin "3") (pinfunction "3_3") (pintype "passive"))
      (node (ref "MSP1") (pin "67") (pinfunction "P9.0/ESICH0/ESITEST0/A8/C8_67") (pintype "bidirectional"))
    )
    (net (code "65") (name "TEST") (class "Default")
      (node (ref "J2") (pin "6") (pinfunction "LVP_6") (pintype "bidirectional"))
      (node (ref "MSP1") (pin "28") (pinfunction "TEST/SBWTCK_28") (pintype "bidirectional"))
    )
    (net (code "66") (name "TRIG") (class "Default")
      (node (ref "J1") (pin "4") (pinfunction "4_4") (pintype "passive"))
      (node (ref "MSP1") (pin "20") (pinfunction "P5.1/TA1.2/S37_20") (pintype "bidirectional"))
    )
    (net (code "67") (name "VCC") (class "Default")
      (node (ref "C6") (pin "1") (pinfunction "1_1") (pintype "passive"))
      (node (ref "C7") (pin "1") (pinfunction "1_1") (pintype "passive"))
      (node (ref "C8") (pin "1") (pinfunction "1_1") (pintype "passive"))
      (node (ref "C9") (pin "1") (pinfunction "1_1") (pintype "passive"))
      (node (ref "HI-LO") (pin "5") (pinfunction "V+_5") (pintype "power_in"))
      (node (ref "LO-HI") (pin "5") (pinfunction "V+_5") (pintype "power_in"))
      (node (ref "MSP1") (pin "27") (pinfunction "DVCC1_27") (pintype "bidirectional"))
      (node (ref "MSP1") (pin "58") (pinfunction "DVCC2_58") (pintype "bidirectional"))
      (node (ref "MSP1") (pin "79") (pinfunction "AVCC1_79") (pintype "bidirectional"))
      (node (ref "MSP1") (pin "99") (pinfunction "DVCC3_99") (pintype "bidirectional"))
      (node (ref "R11") (pin "2") (pinfunction "2_2") (pintype "passive"))
      (node (ref "R16") (pin "2") (pinfunction "2_2") (pintype "passive"))
      (node (ref "R17") (pin "2") (pinfunction "2_2") (pintype "passive"))
      (node (ref "R18") (pin "2") (pinfunction "2_2") (pintype "passive"))
      (node (ref "R3") (pin "1") (pinfunction "1_1") (pintype "passive"))
      (node (ref "R8") (pin "1") (pinfunction "1_1") (pintype "passive"))
      (node (ref "R9") (pin "1") (pinfunction "1_1") (pintype "passive"))
      (node (ref "S1") (pin "2") (pinfunction "P_2") (pintype "passive"))
      (node (ref "U3") (pin "13") (pinfunction "VCC_13") (pintype "bidirectional"))
      (node (ref "U4") (pin "1") (pinfunction "VIN_1") (pintype "bidirectional"))
    )
    (net (code "68") (name "VIN") (class "Default")
      (node (ref "J2") (pin "4") (pinfunction "ICSP_DAT/PGD_4") (pintype "bidirectional"))
      (node (ref "R22") (pin "1") (pinfunction "1_1") (pintype "passive"))
      (node (ref "R24") (pin "1") (pinfunction "1_1") (pintype "passive"))
      (node (ref "U1") (pin "1") (pinfunction "CE_1") (pintype "bidirectional"))
      (node (ref "U1") (pin "4") (pinfunction "VIN_4") (pintype "bidirectional"))
      (node (ref "U10") (pin "8") (pinfunction "VCC+_8") (pintype "bidirectional"))
      (node (ref "U2") (pin "4") (pinfunction "OUT_4") (pintype "bidirectional"))
      (node (ref "U5") (pin "1") (pinfunction "VDD_1") (pintype "bidirectional"))
      (node (ref "U7") (pin "8") (pinfunction "VCC+_8") (pintype "bidirectional"))
      (node (ref "U8") (pin "1") (pinfunction "VDD_1") (pintype "bidirectional"))
    )
    (net (code "69") (name "WP_CTRL_ECHO") (class "Default")
      (node (ref "MSP1") (pin "14") (pinfunction "P2.4/TB0.3/COM4/S43_14") (pintype "bidirectional"))
      (node (ref "U5") (pin "9") (pinfunction "WP_9") (pintype "bidirectional"))
    )
    (net (code "70") (name "WP_CTRL_RADIO") (class "Default")
      (node (ref "MSP1") (pin "11") (pinfunction "P6.4/TB0.0/COM1_11") (pintype "bidirectional"))
      (node (ref "U8") (pin "9") (pinfunction "WP_9") (pintype "bidirectional"))
    )
    (net (code "71") (name "unconnected-(MSP1-ESICI-Pad77)") (class "Default")
      (node (ref "MSP1") (pin "77") (pinfunction "ESICI_77") (pintype "bidirectional"))
    )
    (net (code "72") (name "unconnected-(MSP1-ESICOM-Pad78)") (class "Default")
      (node (ref "MSP1") (pin "78") (pinfunction "ESICOM_78") (pintype "bidirectional"))
    )
    (net (code "73") (name "unconnected-(MSP1-ESIVCC-Pad75)") (class "Default")
      (node (ref "MSP1") (pin "75") (pinfunction "ESIVCC_75") (pintype "bidirectional"))
    )
    (net (code "74") (name "unconnected-(MSP1-ESIVSS-Pad76)") (class "Default")
      (node (ref "MSP1") (pin "76") (pinfunction "ESIVSS_76") (pintype "bidirectional"))
    )
    (net (code "75") (name "unconnected-(MSP1-P1.1{slash}TA0.2{slash}TA1CLK{slash}COUT{slash}A1{slash}C1{slash}VREF+{slash}VEREF+-Pad65)") (class "Default")
      (node (ref "MSP1") (pin "65") (pinfunction "P1.1/TA0.2/TA1CLK/COUT/A1/C1/VREF+/VEREF+_65") (pintype "bidirectional"))
    )
    (net (code "76") (name "unconnected-(MSP1-P1.2{slash}TA1.1{slash}TA0CLK{slash}COUT{slash}A2{slash}C2-Pad64)") (class "Default")
      (node (ref "MSP1") (pin "64") (pinfunction "P1.2/TA1.1/TA0CLK/COUT/A2/C2_64") (pintype "bidirectional"))
    )
    (net (code "77") (name "unconnected-(MSP1-P1.3{slash}TA1.2{slash}ESITEST4{slash}A3{slash}C3-Pad63)") (class "Default")
      (node (ref "MSP1") (pin "63") (pinfunction "P1.3/TA1.2/ESITEST4/A3/C3_63") (pintype "bidirectional"))
    )
    (net (code "78") (name "unconnected-(MSP1-P2.0{slash}UCA0SIMO{slash}UCA0TXD{slash}TB0.6{slash}TB0CLK-Pad51)") (class "Default")
      (node (ref "MSP1") (pin "51") (pinfunction "P2.0/UCA0SIMO/UCA0TXD/TB0.6/TB0CLK_51") (pintype "bidirectional"))
    )
    (net (code "79") (name "unconnected-(MSP1-P2.1{slash}UCA0SOMI{slash}UCA0RXD{slash}TB0.5{slash}DMAE0-Pad50)") (class "Default")
      (node (ref "MSP1") (pin "50") (pinfunction "P2.1/UCA0SOMI/UCA0RXD/TB0.5/DMAE0_50") (pintype "bidirectional"))
    )
    (net (code "80") (name "unconnected-(MSP1-P2.2{slash}UCA0CLK{slash}TB0.4{slash}RTCCLK-Pad49)") (class "Default")
      (node (ref "MSP1") (pin "49") (pinfunction "P2.2/UCA0CLK/TB0.4/RTCCLK_49") (pintype "bidirectional"))
    )
    (net (code "81") (name "unconnected-(MSP1-P2.3{slash}UCA0STE{slash}TB0OUTH-Pad48)") (class "Default")
      (node (ref "MSP1") (pin "48") (pinfunction "P2.3/UCA0STE/TB0OUTH_48") (pintype "bidirectional"))
    )
    (net (code "82") (name "unconnected-(MSP1-P3.0{slash}UCB1CLK{slash}S34-Pad23)") (class "Default")
      (node (ref "MSP1") (pin "23") (pinfunction "P3.0/UCB1CLK/S34_23") (pintype "bidirectional"))
    )
    (net (code "83") (name "unconnected-(MSP1-P3.3{slash}TA1.1{slash}TB0CLK{slash}S26-Pad39)") (class "Default")
      (node (ref "MSP1") (pin "39") (pinfunction "P3.3/TA1.1/TB0CLK/S26_39") (pintype "bidirectional"))
    )
    (net (code "84") (name "unconnected-(MSP1-P3.4{slash}UCA1SIMO{slash}UCA1TXD{slash}TB0.0{slash}S25-Pad40)") (class "Default")
      (node (ref "MSP1") (pin "40") (pinfunction "P3.4/UCA1SIMO/UCA1TXD/TB0.0/S25_40") (pintype "bidirectional"))
    )
    (net (code "85") (name "unconnected-(MSP1-P3.5{slash}UCA1SOMI{slash}UCA1RXD{slash}TB0.1{slash}S24-Pad41)") (class "Default")
      (node (ref "MSP1") (pin "41") (pinfunction "P3.5/UCA1SOMI/UCA1RXD/TB0.1/S24_41") (pintype "bidirectional"))
    )
    (net (code "86") (name "unconnected-(MSP1-P3.6{slash}UCA1CLK{slash}TB0.2{slash}S23-Pad42)") (class "Default")
      (node (ref "MSP1") (pin "42") (pinfunction "P3.6/UCA1CLK/TB0.2/S23_42") (pintype "bidirectional"))
    )
    (net (code "87") (name "unconnected-(MSP1-P3.7{slash}UCA1STE{slash}TB0.3{slash}S22-Pad43)") (class "Default")
      (node (ref "MSP1") (pin "43") (pinfunction "P3.7/UCA1STE/TB0.3/S22_43") (pintype "bidirectional"))
    )
    (net (code "88") (name "unconnected-(MSP1-P4.0{slash}UCB1SIMO{slash}UCB1SDA{slash}MCLK{slash}S3-Pad96)") (class "Default")
      (node (ref "MSP1") (pin "96") (pinfunction "P4.0/UCB1SIMO/UCB1SDA/MCLK/S3_96") (pintype "bidirectional"))
    )
    (net (code "89") (name "unconnected-(MSP1-P4.1{slash}UCB1SOMI{slash}UCB1SCL{slash}ACLK{slash}S2-Pad97)") (class "Default")
      (node (ref "MSP1") (pin "97") (pinfunction "P4.1/UCB1SOMI/UCB1SCL/ACLK/S2_97") (pintype "bidirectional"))
    )
    (net (code "90") (name "unconnected-(MSP1-P4.2{slash}UCA0SIMO{slash}UCA0TXD{slash}UCB1CLK-Pad100)") (class "Default")
      (node (ref "MSP1") (pin "100") (pinfunction "P4.2/UCA0SIMO/UCA0TXD/UCB1CLK_100") (pintype "bidirectional"))
    )
    (net (code "91") (name "unconnected-(MSP1-P4.3{slash}UCA0SOMI{slash}UCA0RXD{slash}UCB1STE-Pad1)") (class "Default")
      (node (ref "MSP1") (pin "1") (pinfunction "P4.3/UCA0SOMI/UCA0RXD/UCB1STE_1") (pintype "bidirectional"))
    )
    (net (code "92") (name "unconnected-(MSP1-P4.4{slash}UCB1STE{slash}TA1CLK{slash}S8-Pad91)") (class "Default")
      (node (ref "MSP1") (pin "91") (pinfunction "P4.4/UCB1STE/TA1CLK/S8_91") (pintype "bidirectional"))
    )
    (net (code "93") (name "unconnected-(MSP1-P4.5{slash}UCB1CLK{slash}TA1.0{slash}S7-Pad92)") (class "Default")
      (node (ref "MSP1") (pin "92") (pinfunction "P4.5/UCB1CLK/TA1.0/S7_92") (pintype "bidirectional"))
    )
    (net (code "94") (name "unconnected-(MSP1-P4.6{slash}UCB1SIMO{slash}UCB1SDA{slash}TA1.1{slash}S6-Pad93)") (class "Default")
      (node (ref "MSP1") (pin "93") (pinfunction "P4.6/UCB1SIMO/UCB1SDA/TA1.1/S6_93") (pintype "bidirectional"))
    )
    (net (code "95") (name "unconnected-(MSP1-P4.7{slash}UCB1SOMI{slash}UCB1SCL{slash}TA1.2{slash}S5-Pad94)") (class "Default")
      (node (ref "MSP1") (pin "94") (pinfunction "P4.7/UCB1SOMI/UCB1SCL/TA1.2/S5_94") (pintype "bidirectional"))
    )
    (net (code "96") (name "unconnected-(MSP1-P5.2{slash}TA1.0{slash}TA1CLK{slash}ACLK{slash}S36-Pad21)") (class "Default")
      (node (ref "MSP1") (pin "21") (pinfunction "P5.2/TA1.0/TA1CLK/ACLK/S36_21") (pintype "bidirectional"))
    )
    (net (code "97") (name "unconnected-(MSP1-P5.3{slash}UCB1STE{slash}S35-Pad22)") (class "Default")
      (node (ref "MSP1") (pin "22") (pinfunction "P5.3/UCB1STE/S35_22") (pintype "bidirectional"))
    )
    (net (code "98") (name "unconnected-(MSP1-P5.4{slash}UCA1SIMO{slash}UCA1TXD{slash}S12-Pad87)") (class "Default")
      (node (ref "MSP1") (pin "87") (pinfunction "P5.4/UCA1SIMO/UCA1TXD/S12_87") (pintype "bidirectional"))
    )
    (net (code "99") (name "unconnected-(MSP1-P5.5{slash}UCA1SOMI{slash}UCA1RXD{slash}S11-Pad88)") (class "Default")
      (node (ref "MSP1") (pin "88") (pinfunction "P5.5/UCA1SOMI/UCA1RXD/S11_88") (pintype "bidirectional"))
    )
    (net (code "100") (name "unconnected-(MSP1-P5.6{slash}UCA1CLK{slash}S10-Pad89)") (class "Default")
      (node (ref "MSP1") (pin "89") (pinfunction "P5.6/UCA1CLK/S10_89") (pintype "bidirectional"))
    )
    (net (code "101") (name "unconnected-(MSP1-P5.7{slash}UCA1STE{slash}TB0CLK{slash}S9-Pad90)") (class "Default")
      (node (ref "MSP1") (pin "90") (pinfunction "P5.7/UCA1STE/TB0CLK/S9_90") (pintype "bidirectional"))
    )
    (net (code "102") (name "unconnected-(MSP1-P6.7{slash}TA0CLK{slash}S31-Pad34)") (class "Default")
      (node (ref "MSP1") (pin "34") (pinfunction "P6.7/TA0CLK/S31_34") (pintype "bidirectional"))
    )
    (net (code "103") (name "unconnected-(MSP1-P7.0{slash}TA0CLK{slash}S17-Pad52)") (class "Default")
      (node (ref "MSP1") (pin "52") (pinfunction "P7.0/TA0CLK/S17_52") (pintype "bidirectional"))
    )
    (net (code "104") (name "unconnected-(MSP1-P7.1{slash}TA0.0{slash}S16-Pad53)") (class "Default")
      (node (ref "MSP1") (pin "53") (pinfunction "P7.1/TA0.0/S16_53") (pintype "bidirectional"))
    )
    (net (code "105") (name "unconnected-(MSP1-P7.2{slash}TA0.1{slash}S15-Pad54)") (class "Default")
      (node (ref "MSP1") (pin "54") (pinfunction "P7.2/TA0.1/S15_54") (pintype "bidirectional"))
    )
    (net (code "106") (name "unconnected-(MSP1-P7.3{slash}TA0.2{slash}S14-Pad55)") (class "Default")
      (node (ref "MSP1") (pin "55") (pinfunction "P7.3/TA0.2/S14_55") (pintype "bidirectional"))
    )
    (net (code "107") (name "unconnected-(MSP1-P7.4{slash}SMCLK{slash}S13-Pad56)") (class "Default")
      (node (ref "MSP1") (pin "56") (pinfunction "P7.4/SMCLK/S13_56") (pintype "bidirectional"))
    )
    (net (code "108") (name "unconnected-(MSP1-P7.5{slash}TA0.2{slash}S30-Pad35)") (class "Default")
      (node (ref "MSP1") (pin "35") (pinfunction "P7.5/TA0.2/S30_35") (pintype "bidirectional"))
    )
    (net (code "109") (name "unconnected-(MSP1-P7.6{slash}TA0.1{slash}S29-Pad36)") (class "Default")
      (node (ref "MSP1") (pin "36") (pinfunction "P7.6/TA0.1/S29_36") (pintype "bidirectional"))
    )
    (net (code "110") (name "unconnected-(MSP1-P7.7{slash}TA1.2{slash}TB0OUTH{slash}S27-Pad38)") (class "Default")
      (node (ref "MSP1") (pin "38") (pinfunction "P7.7/TA1.2/TB0OUTH/S27_38") (pintype "bidirectional"))
    )
    (net (code "111") (name "unconnected-(MSP1-P8.0{slash}RTCCLK{slash}S21-Pad44)") (class "Default")
      (node (ref "MSP1") (pin "44") (pinfunction "P8.0/RTCCLK/S21_44") (pintype "bidirectional"))
    )
    (net (code "112") (name "unconnected-(MSP1-P8.1{slash}DMAE0{slash}S20-Pad45)") (class "Default")
      (node (ref "MSP1") (pin "45") (pinfunction "P8.1/DMAE0/S20_45") (pintype "bidirectional"))
    )
    (net (code "113") (name "unconnected-(MSP1-P8.2{slash}S19-Pad46)") (class "Default")
      (node (ref "MSP1") (pin "46") (pinfunction "P8.2/S19_46") (pintype "bidirectional"))
    )
    (net (code "114") (name "unconnected-(MSP1-P8.3{slash}MCLK{slash}S18-Pad47)") (class "Default")
      (node (ref "MSP1") (pin "47") (pinfunction "P8.3/MCLK/S18_47") (pintype "bidirectional"))
    )
    (net (code "115") (name "unconnected-(MSP1-P8.4{slash}A7{slash}C7-Pad59)") (class "Default")
      (node (ref "MSP1") (pin "59") (pinfunction "P8.4/A7/C7_59") (pintype "bidirectional"))
    )
    (net (code "116") (name "unconnected-(MSP1-P8.5{slash}A6{slash}C6-Pad60)") (class "Default")
      (node (ref "MSP1") (pin "60") (pinfunction "P8.5/A6/C6_60") (pintype "bidirectional"))
    )
    (net (code "117") (name "unconnected-(MSP1-P8.6{slash}A5{slash}C5-Pad61)") (class "Default")
      (node (ref "MSP1") (pin "61") (pinfunction "P8.6/A5/C5_61") (pintype "bidirectional"))
    )
    (net (code "118") (name "unconnected-(MSP1-P8.7{slash}A4{slash}C4-Pad62)") (class "Default")
      (node (ref "MSP1") (pin "62") (pinfunction "P8.7/A4/C4_62") (pintype "bidirectional"))
    )
    (net (code "119") (name "unconnected-(MSP1-P10.0{slash}SMCLK{slash}S4-Pad95)") (class "Default")
      (node (ref "MSP1") (pin "95") (pinfunction "P10.0/SMCLK/S4_95") (pintype "bidirectional"))
    )
    (net (code "120") (name "unconnected-(MSP1-P10.1{slash}TA0.0{slash}S28-Pad37)") (class "Default")
      (node (ref "MSP1") (pin "37") (pinfunction "P10.1/TA0.0/S28_37") (pintype "bidirectional"))
    )
    (net (code "121") (name "unconnected-(MSP1-P10.2{slash}TA1.0{slash}SMCLK{slash}S39-Pad18)") (class "Default")
      (node (ref "MSP1") (pin "18") (pinfunction "P10.2/TA1.0/SMCLK/S39_18") (pintype "bidirectional"))
    )
    (net (code "122") (name "unconnected-(MSP1-PJ.0{slash}TDO{slash}TB0OUTH{slash}SMCLK{slash}SRSCG1-Pad30)") (class "Default")
      (node (ref "MSP1") (pin "30") (pinfunction "PJ.0/TDO/TB0OUTH/SMCLK/SRSCG1_30") (pintype "bidirectional"))
    )
    (net (code "123") (name "unconnected-(MSP1-PJ.1{slash}TDI{slash}TCLK{slash}MCLK{slash}SRSCG-Pad31)") (class "Default")
      (node (ref "MSP1") (pin "31") (pinfunction "PJ.1/TDI/TCLK/MCLK/SRSCG_31") (pintype "bidirectional"))
    )
    (net (code "124") (name "unconnected-(MSP1-PJ.2{slash}TMS{slash}ACLK{slash}SROSCOFF-Pad32)") (class "Default")
      (node (ref "MSP1") (pin "32") (pinfunction "PJ.2/TMS/ACLK/SROSCOFF_32") (pintype "bidirectional"))
    )
    (net (code "125") (name "unconnected-(MSP1-PJ.3{slash}TCK{slash}COUT{slash}SRCPUOFF-Pad33)") (class "Default")
      (node (ref "MSP1") (pin "33") (pinfunction "PJ.3/TCK/COUT/SRCPUOFF_33") (pintype "bidirectional"))
    )
    (net (code "126") (name "unconnected-(MSP1-PJ.4{slash}LFXIN-Pad84)") (class "Default")
      (node (ref "MSP1") (pin "84") (pinfunction "PJ.4/LFXIN_84") (pintype "bidirectional"))
    )
    (net (code "127") (name "unconnected-(MSP1-PJ.5{slash}LFXOUT-Pad85)") (class "Default")
      (node (ref "MSP1") (pin "85") (pinfunction "PJ.5/LFXOUT_85") (pintype "bidirectional"))
    )
    (net (code "128") (name "unconnected-(MSP1-PJ.6{slash}HFXIN-Pad82)") (class "Default")
      (node (ref "MSP1") (pin "82") (pinfunction "PJ.6/HFXIN_82") (pintype "bidirectional"))
    )
    (net (code "129") (name "unconnected-(MSP1-PJ.7{slash}HFXOUT-Pad81)") (class "Default")
      (node (ref "MSP1") (pin "81") (pinfunction "PJ.7/HFXOUT_81") (pintype "bidirectional"))
    )
    (net (code "130") (name "unconnected-(MSP1-R33{slash}LCDCAP-Pad6)") (class "Default")
      (node (ref "MSP1") (pin "6") (pinfunction "R33/LCDCAP_6") (pintype "bidirectional"))
    )
    (net (code "131") (name "unconnected-(U3-AF-Pad14)") (class "Default")
      (node (ref "U3") (pin "14") (pinfunction "AF_14") (pintype "bidirectional"))
    )
    (net (code "132") (name "unconnected-(U3-FOUT{slash}IRQ-Pad11)") (class "Default")
      (node (ref "U3") (pin "11") (pinfunction "FOUT/IRQ_11") (pintype "bidirectional"))
    )
    (net (code "133") (name "unconnected-(U3-IRQ2-Pad4)") (class "Default")
      (node (ref "U3") (pin "4") (pinfunction "IRQ2_4") (pintype "bidirectional"))
    )
    (net (code "134") (name "unconnected-(U3-TIRQ-Pad12)") (class "Default")
      (node (ref "U3") (pin "12") (pinfunction "TIRQ_12") (pintype "bidirectional"))
    )
    (net (code "135") (name "unconnected-(U3-XI-Pad16)") (class "Default")
      (node (ref "U3") (pin "16") (pinfunction "XI_16") (pintype "bidirectional"))
    )
    (net (code "136") (name "unconnected-(U3-XO-Pad15)") (class "Default")
      (node (ref "U3") (pin "15") (pinfunction "XO_15") (pintype "bidirectional"))
    )
    (net (code "137") (name "unconnected-(U5-HA-Pad15)") (class "Default")
      (node (ref "U5") (pin "15") (pinfunction "HA_15") (pintype "passive"))
    )
    (net (code "138") (name "unconnected-(U5-HB-Pad12)") (class "Default")
      (node (ref "U5") (pin "12") (pinfunction "HB_12") (pintype "bidirectional"))
    )
    (net (code "139") (name "unconnected-(U8-HA-Pad15)") (class "Default")
      (node (ref "U8") (pin "15") (pinfunction "HA_15") (pintype "passive"))
    )
    (net (code "140") (name "unconnected-(U8-HB-Pad12)") (class "Default")
      (node (ref "U8") (pin "12") (pinfunction "HB_12") (pintype "bidirectional"))
    )
  )
)
